# F800GSDayLight.net
KiCad netlist of a schematic drawn in Altium Designer
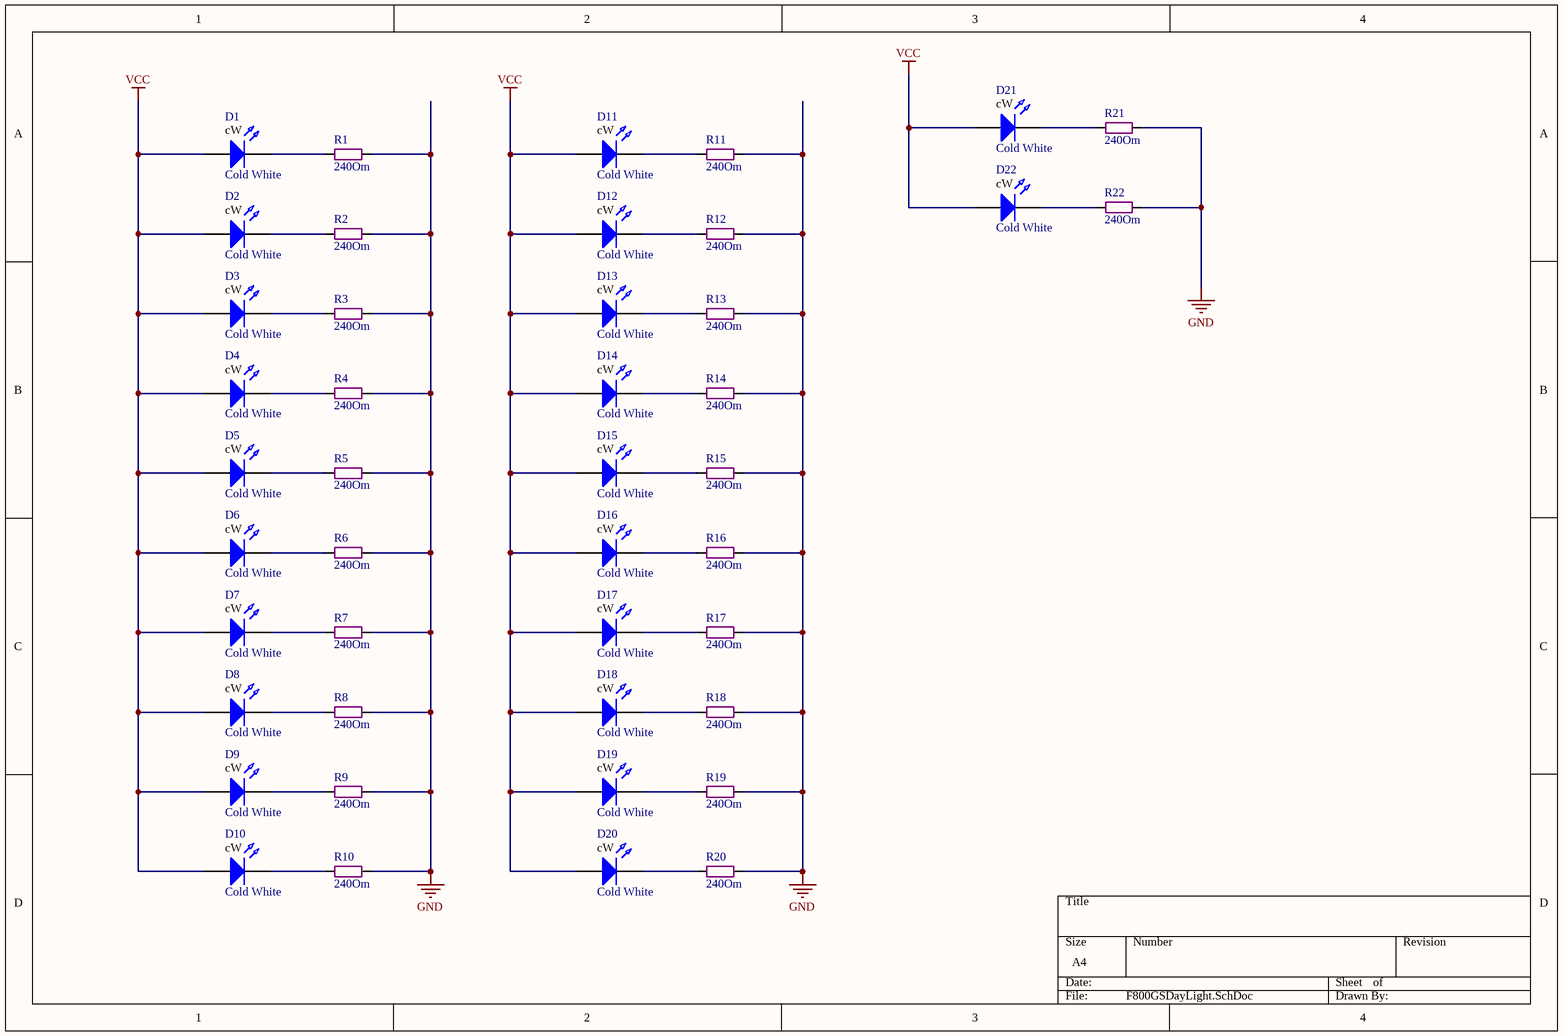
[diagram p0: F800GSDayLight.SchDoc]

(export (version "E")
  (design (tool "Eeschema 10.0.6"))
  (components
    (comp (ref "D1")
      (value "Cold White")
      (footprint "LED:LED SMD 5050 White compact R")
      (description "?3v ?20mA")
      (libsource (lib "LED") (part "Led SMD White Cold"))
    )
    (comp (ref "D2")
      (value "Cold White")
      (footprint "LED:LED SMD 5050 White compact R")
      (description "?3v ?20mA")
      (libsource (lib "LED") (part "Led SMD White Cold"))
    )
    (comp (ref "D3")
      (value "Cold White")
      (footprint "LED:LED SMD 5050 White compact R")
      (description "?3v ?20mA")
      (libsource (lib "LED") (part "Led SMD White Cold"))
    )
    (comp (ref "D4")
      (value "Cold White")
      (footprint "LED:LED SMD 5050 White compact R")
      (description "?3v ?20mA")
      (libsource (lib "LED") (part "Led SMD White Cold"))
    )
    (comp (ref "D5")
      (value "Cold White")
      (footprint "LED:LED SMD 5050 White compact R")
      (description "?3v ?20mA")
      (libsource (lib "LED") (part "Led SMD White Cold"))
    )
    (comp (ref "D6")
      (value "Cold White")
      (footprint "LED:LED SMD 5050 White compact R")
      (description "?3v ?20mA")
      (libsource (lib "LED") (part "Led SMD White Cold"))
    )
    (comp (ref "D7")
      (value "Cold White")
      (footprint "LED:LED SMD 5050 White compact R")
      (description "?3v ?20mA")
      (libsource (lib "LED") (part "Led SMD White Cold"))
    )
    (comp (ref "D8")
      (value "Cold White")
      (footprint "LED:LED SMD 5050 White compact R")
      (description "?3v ?20mA")
      (libsource (lib "LED") (part "Led SMD White Cold"))
    )
    (comp (ref "D9")
      (value "Cold White")
      (footprint "LED:LED SMD 5050 White compact R")
      (description "?3v ?20mA")
      (libsource (lib "LED") (part "Led SMD White Cold"))
    )
    (comp (ref "D10")
      (value "Cold White")
      (footprint "LED:LED SMD 5050 White compact R")
      (description "?3v ?20mA")
      (libsource (lib "LED") (part "Led SMD White Cold"))
    )
    (comp (ref "D11")
      (value "Cold White")
      (footprint "LED:LED SMD 5050 White compact R")
      (description "?3v ?20mA")
      (libsource (lib "LED") (part "Led SMD White Cold"))
    )
    (comp (ref "D12")
      (value "Cold White")
      (footprint "LED:LED SMD 5050 White compact R")
      (description "?3v ?20mA")
      (libsource (lib "LED") (part "Led SMD White Cold"))
    )
    (comp (ref "D13")
      (value "Cold White")
      (footprint "LED:LED SMD 5050 White compact R")
      (description "?3v ?20mA")
      (libsource (lib "LED") (part "Led SMD White Cold"))
    )
    (comp (ref "D14")
      (value "Cold White")
      (footprint "LED:LED SMD 5050 White compact R")
      (description "?3v ?20mA")
      (libsource (lib "LED") (part "Led SMD White Cold"))
    )
    (comp (ref "D15")
      (value "Cold White")
      (footprint "LED:LED SMD 5050 White compact R")
      (description "?3v ?20mA")
      (libsource (lib "LED") (part "Led SMD White Cold"))
    )
    (comp (ref "D16")
      (value "Cold White")
      (footprint "LED:LED SMD 5050 White compact R")
      (description "?3v ?20mA")
      (libsource (lib "LED") (part "Led SMD White Cold"))
    )
    (comp (ref "D17")
      (value "Cold White")
      (footprint "LED:LED SMD 5050 White compact R")
      (description "?3v ?20mA")
      (libsource (lib "LED") (part "Led SMD White Cold"))
    )
    (comp (ref "D18")
      (value "Cold White")
      (footprint "LED:LED SMD 5050 White compact R")
      (description "?3v ?20mA")
      (libsource (lib "LED") (part "Led SMD White Cold"))
    )
    (comp (ref "D19")
      (value "Cold White")
      (footprint "LED:LED SMD 5050 White compact R")
      (description "?3v ?20mA")
      (libsource (lib "LED") (part "Led SMD White Cold"))
    )
    (comp (ref "D20")
      (value "Cold White")
      (footprint "LED:LED SMD 5050 White compact R")
      (description "?3v ?20mA")
      (libsource (lib "LED") (part "Led SMD White Cold"))
    )
    (comp (ref "D21")
      (value "Cold White")
      (footprint "LED:LED SMD 5050 White compact R")
      (description "?3v ?20mA")
      (libsource (lib "LED") (part "Led SMD White Cold"))
    )
    (comp (ref "D22")
      (value "Cold White")
      (footprint "LED:LED SMD 5050 White compact R")
      (description "?3v ?20mA")
      (libsource (lib "LED") (part "Led SMD White Cold"))
    )
    (comp (ref "R1")
      (value "240Om")
      (footprint "PassiveComponents:SMD 0805 (2012)")
      (libsource (lib "PassiveComponents") (part "Res All Types"))
    )
    (comp (ref "R2")
      (value "240Om")
      (footprint "PassiveComponents:SMD 0805 (2012)")
      (libsource (lib "PassiveComponents") (part "Res All Types"))
    )
    (comp (ref "R3")
      (value "240Om")
      (footprint "PassiveComponents:SMD 0805 (2012)")
      (libsource (lib "PassiveComponents") (part "Res All Types"))
    )
    (comp (ref "R4")
      (value "240Om")
      (footprint "PassiveComponents:SMD 0805 (2012)")
      (libsource (lib "PassiveComponents") (part "Res All Types"))
    )
    (comp (ref "R5")
      (value "240Om")
      (footprint "PassiveComponents:SMD 0805 (2012)")
      (libsource (lib "PassiveComponents") (part "Res All Types"))
    )
    (comp (ref "R6")
      (value "240Om")
      (footprint "PassiveComponents:SMD 0805 (2012)")
      (libsource (lib "PassiveComponents") (part "Res All Types"))
    )
    (comp (ref "R7")
      (value "240Om")
      (footprint "PassiveComponents:SMD 0805 (2012)")
      (libsource (lib "PassiveComponents") (part "Res All Types"))
    )
    (comp (ref "R8")
      (value "240Om")
      (footprint "PassiveComponents:SMD 0805 (2012)")
      (libsource (lib "PassiveComponents") (part "Res All Types"))
    )
    (comp (ref "R9")
      (value "240Om")
      (footprint "PassiveComponents:SMD 0805 (2012)")
      (libsource (lib "PassiveComponents") (part "Res All Types"))
    )
    (comp (ref "R10")
      (value "240Om")
      (footprint "PassiveComponents:SMD 0805 (2012)")
      (libsource (lib "PassiveComponents") (part "Res All Types"))
    )
    (comp (ref "R11")
      (value "240Om")
      (footprint "PassiveComponents:SMD 0805 (2012)")
      (libsource (lib "PassiveComponents") (part "Res All Types"))
    )
    (comp (ref "R12")
      (value "240Om")
      (footprint "PassiveComponents:SMD 0805 (2012)")
      (libsource (lib "PassiveComponents") (part "Res All Types"))
    )
    (comp (ref "R13")
      (value "240Om")
      (footprint "PassiveComponents:SMD 0805 (2012)")
      (libsource (lib "PassiveComponents") (part "Res All Types"))
    )
    (comp (ref "R14")
      (value "240Om")
      (footprint "PassiveComponents:SMD 0805 (2012)")
      (libsource (lib "PassiveComponents") (part "Res All Types"))
    )
    (comp (ref "R15")
      (value "240Om")
      (footprint "PassiveComponents:SMD 0805 (2012)")
      (libsource (lib "PassiveComponents") (part "Res All Types"))
    )
    (comp (ref "R16")
      (value "240Om")
      (footprint "PassiveComponents:SMD 0805 (2012)")
      (libsource (lib "PassiveComponents") (part "Res All Types"))
    )
    (comp (ref "R17")
      (value "240Om")
      (footprint "PassiveComponents:SMD 0805 (2012)")
      (libsource (lib "PassiveComponents") (part "Res All Types"))
    )
    (comp (ref "R18")
      (value "240Om")
      (footprint "PassiveComponents:SMD 0805 (2012)")
      (libsource (lib "PassiveComponents") (part "Res All Types"))
    )
    (comp (ref "R19")
      (value "240Om")
      (footprint "PassiveComponents:SMD 0805 (2012)")
      (libsource (lib "PassiveComponents") (part "Res All Types"))
    )
    (comp (ref "R20")
      (value "240Om")
      (footprint "PassiveComponents:SMD 0805 (2012)")
      (libsource (lib "PassiveComponents") (part "Res All Types"))
    )
    (comp (ref "R21")
      (value "240Om")
      (footprint "PassiveComponents:SMD 0805 (2012)")
      (libsource (lib "PassiveComponents") (part "Res All Types"))
    )
    (comp (ref "R22")
      (value "240Om")
      (footprint "PassiveComponents:SMD 0805 (2012)")
      (libsource (lib "PassiveComponents") (part "Res All Types"))
    )
  )
  (nets
    (net (code "1") (name "GND") (class "Default")
      (node (ref "R1") (pin "2") (pinfunction "2_2") (pintype "passive"))
      (node (ref "R10") (pin "2") (pinfunction "2_2") (pintype "passive"))
      (node (ref "R11") (pin "2") (pinfunction "2_2") (pintype "passive"))
      (node (ref "R12") (pin "2") (pinfunction "2_2") (pintype "passive"))
      (node (ref "R13") (pin "2") (pinfunction "2_2") (pintype "passive"))
      (node (ref "R14") (pin "2") (pinfunction "2_2") (pintype "passive"))
      (node (ref "R15") (pin "2") (pinfunction "2_2") (pintype "passive"))
      (node (ref "R16") (pin "2") (pinfunction "2_2") (pintype "passive"))
      (node (ref "R17") (pin "2") (pinfunction "2_2") (pintype "passive"))
      (node (ref "R18") (pin "2") (pinfunction "2_2") (pintype "passive"))
      (node (ref "R19") (pin "2") (pinfunction "2_2") (pintype "passive"))
      (node (ref "R2") (pin "2") (pinfunction "2_2") (pintype "passive"))
      (node (ref "R20") (pin "2") (pinfunction "2_2") (pintype "passive"))
      (node (ref "R21") (pin "2") (pinfunction "2_2") (pintype "passive"))
      (node (ref "R22") (pin "2") (pinfunction "2_2") (pintype "passive"))
      (node (ref "R3") (pin "2") (pinfunction "2_2") (pintype "passive"))
      (node (ref "R4") (pin "2") (pinfunction "2_2") (pintype "passive"))
      (node (ref "R5") (pin "2") (pinfunction "2_2") (pintype "passive"))
      (node (ref "R6") (pin "2") (pinfunction "2_2") (pintype "passive"))
      (node (ref "R7") (pin "2") (pinfunction "2_2") (pintype "passive"))
      (node (ref "R8") (pin "2") (pinfunction "2_2") (pintype "passive"))
      (node (ref "R9") (pin "2") (pinfunction "2_2") (pintype "passive"))
    )
    (net (code "2") (name "Net-(D1-PadK)") (class "Default")
      (node (ref "D1") (pin "K") (pinfunction "K_K") (pintype "passive"))
      (node (ref "R1") (pin "1") (pinfunction "1_1") (pintype "passive"))
    )
    (net (code "3") (name "Net-(D2-PadK)") (class "Default")
      (node (ref "D2") (pin "K") (pinfunction "K_K") (pintype "passive"))
      (node (ref "R2") (pin "1") (pinfunction "1_1") (pintype "passive"))
    )
    (net (code "4") (name "Net-(D3-PadK)") (class "Default")
      (node (ref "D3") (pin "K") (pinfunction "K_K") (pintype "passive"))
      (node (ref "R3") (pin "1") (pinfunction "1_1") (pintype "passive"))
    )
    (net (code "5") (name "Net-(D4-PadK)") (class "Default")
      (node (ref "D4") (pin "K") (pinfunction "K_K") (pintype "passive"))
      (node (ref "R4") (pin "1") (pinfunction "1_1") (pintype "passive"))
    )
    (net (code "6") (name "Net-(D5-PadK)") (class "Default")
      (node (ref "D5") (pin "K") (pinfunction "K_K") (pintype "passive"))
      (node (ref "R5") (pin "1") (pinfunction "1_1") (pintype "passive"))
    )
    (net (code "7") (name "Net-(D6-PadK)") (class "Default")
      (node (ref "D6") (pin "K") (pinfunction "K_K") (pintype "passive"))
      (node (ref "R6") (pin "1") (pinfunction "1_1") (pintype "passive"))
    )
    (net (code "8") (name "Net-(D7-PadK)") (class "Default")
      (node (ref "D7") (pin "K") (pinfunction "K_K") (pintype "passive"))
      (node (ref "R7") (pin "1") (pinfunction "1_1") (pintype "passive"))
    )
    (net (code "9") (name "Net-(D8-PadK)") (class "Default")
      (node (ref "D8") (pin "K") (pinfunction "K_K") (pintype "passive"))
      (node (ref "R8") (pin "1") (pinfunction "1_1") (pintype "passive"))
    )
    (net (code "10") (name "Net-(D9-PadK)") (class "Default")
      (node (ref "D9") (pin "K") (pinfunction "K_K") (pintype "passive"))
      (node (ref "R9") (pin "1") (pinfunction "1_1") (pintype "passive"))
    )
    (net (code "11") (name "Net-(D10-PadK)") (class "Default")
      (node (ref "D10") (pin "K") (pinfunction "K_K") (pintype "passive"))
      (node (ref "R10") (pin "1") (pinfunction "1_1") (pintype "passive"))
    )
    (net (code "12") (name "Net-(D11-PadK)") (class "Default")
      (node (ref "D11") (pin "K") (pinfunction "K_K") (pintype "passive"))
      (node (ref "R11") (pin "1") (pinfunction "1_1") (pintype "passive"))
    )
    (net (code "13") (name "Net-(D12-PadK)") (class "Default")
      (node (ref "D12") (pin "K") (pinfunction "K_K") (pintype "passive"))
      (node (ref "R12") (pin "1") (pinfunction "1_1") (pintype "passive"))
    )
    (net (code "14") (name "Net-(D13-PadK)") (class "Default")
      (node (ref "D13") (pin "K") (pinfunction "K_K") (pintype "passive"))
      (node (ref "R13") (pin "1") (pinfunction "1_1") (pintype "passive"))
    )
    (net (code "15") (name "Net-(D14-PadK)") (class "Default")
      (node (ref "D14") (pin "K") (pinfunction "K_K") (pintype "passive"))
      (node (ref "R14") (pin "1") (pinfunction "1_1") (pintype "passive"))
    )
    (net (code "16") (name "Net-(D15-PadK)") (class "Default")
      (node (ref "D15") (pin "K") (pinfunction "K_K") (pintype "passive"))
      (node (ref "R15") (pin "1") (pinfunction "1_1") (pintype "passive"))
    )
    (net (code "17") (name "Net-(D16-PadK)") (class "Default")
      (node (ref "D16") (pin "K") (pinfunction "K_K") (pintype "passive"))
      (node (ref "R16") (pin "1") (pinfunction "1_1") (pintype "passive"))
    )
    (net (code "18") (name "Net-(D17-PadK)") (class "Default")
      (node (ref "D17") (pin "K") (pinfunction "K_K") (pintype "passive"))
      (node (ref "R17") (pin "1") (pinfunction "1_1") (pintype "passive"))
    )
    (net (code "19") (name "Net-(D18-PadK)") (class "Default")
      (node (ref "D18") (pin "K") (pinfunction "K_K") (pintype "passive"))
      (node (ref "R18") (pin "1") (pinfunction "1_1") (pintype "passive"))
    )
    (net (code "20") (name "Net-(D19-PadK)") (class "Default")
      (node (ref "D19") (pin "K") (pinfunction "K_K") (pintype "passive"))
      (node (ref "R19") (pin "1") (pinfunction "1_1") (pintype "passive"))
    )
    (net (code "21") (name "Net-(D20-PadK)") (class "Default")
      (node (ref "D20") (pin "K") (pinfunction "K_K") (pintype "passive"))
      (node (ref "R20") (pin "1") (pinfunction "1_1") (pintype "passive"))
    )
    (net (code "22") (name "Net-(D21-PadK)") (class "Default")
      (node (ref "D21") (pin "K") (pinfunction "K_K") (pintype "passive"))
      (node (ref "R21") (pin "1") (pinfunction "1_1") (pintype "passive"))
    )
    (net (code "23") (name "Net-(D22-PadK)") (class "Default")
      (node (ref "D22") (pin "K") (pinfunction "K_K") (pintype "passive"))
      (node (ref "R22") (pin "1") (pinfunction "1_1") (pintype "passive"))
    )
    (net (code "24") (name "VCC") (class "Default")
      (node (ref "D1") (pin "A") (pinfunction "A_A") (pintype "passive"))
      (node (ref "D10") (pin "A") (pinfunction "A_A") (pintype "passive"))
      (node (ref "D11") (pin "A") (pinfunction "A_A") (pintype "passive"))
      (node (ref "D12") (pin "A") (pinfunction "A_A") (pintype "passive"))
      (node (ref "D13") (pin "A") (pinfunction "A_A") (pintype "passive"))
      (node (ref "D14") (pin "A") (pinfunction "A_A") (pintype "passive"))
      (node (ref "D15") (pin "A") (pinfunction "A_A") (pintype "passive"))
      (node (ref "D16") (pin "A") (pinfunction "A_A") (pintype "passive"))
      (node (ref "D17") (pin "A") (pinfunction "A_A") (pintype "passive"))
      (node (ref "D18") (pin "A") (pinfunction "A_A") (pintype "passive"))
      (node (ref "D19") (pin "A") (pinfunction "A_A") (pintype "passive"))
      (node (ref "D2") (pin "A") (pinfunction "A_A") (pintype "passive"))
      (node (ref "D20") (pin "A") (pinfunction "A_A") (pintype "passive"))
      (node (ref "D21") (pin "A") (pinfunction "A_A") (pintype "passive"))
      (node (ref "D22") (pin "A") (pinfunction "A_A") (pintype "passive"))
      (node (ref "D3") (pin "A") (pinfunction "A_A") (pintype "passive"))
      (node (ref "D4") (pin "A") (pinfunction "A_A") (pintype "passive"))
      (node (ref "D5") (pin "A") (pinfunction "A_A") (pintype "passive"))
      (node (ref "D6") (pin "A") (pinfunction "A_A") (pintype "passive"))
      (node (ref "D7") (pin "A") (pinfunction "A_A") (pintype "passive"))
      (node (ref "D8") (pin "A") (pinfunction "A_A") (pintype "passive"))
      (node (ref "D9") (pin "A") (pinfunction "A_A") (pintype "passive"))
    )
  )
)
